# EasyEDA_SCH_BL28Z-3005ZSA04Y_A_Version_B.net
KiCad netlist of a schematic drawn in EasyEDA
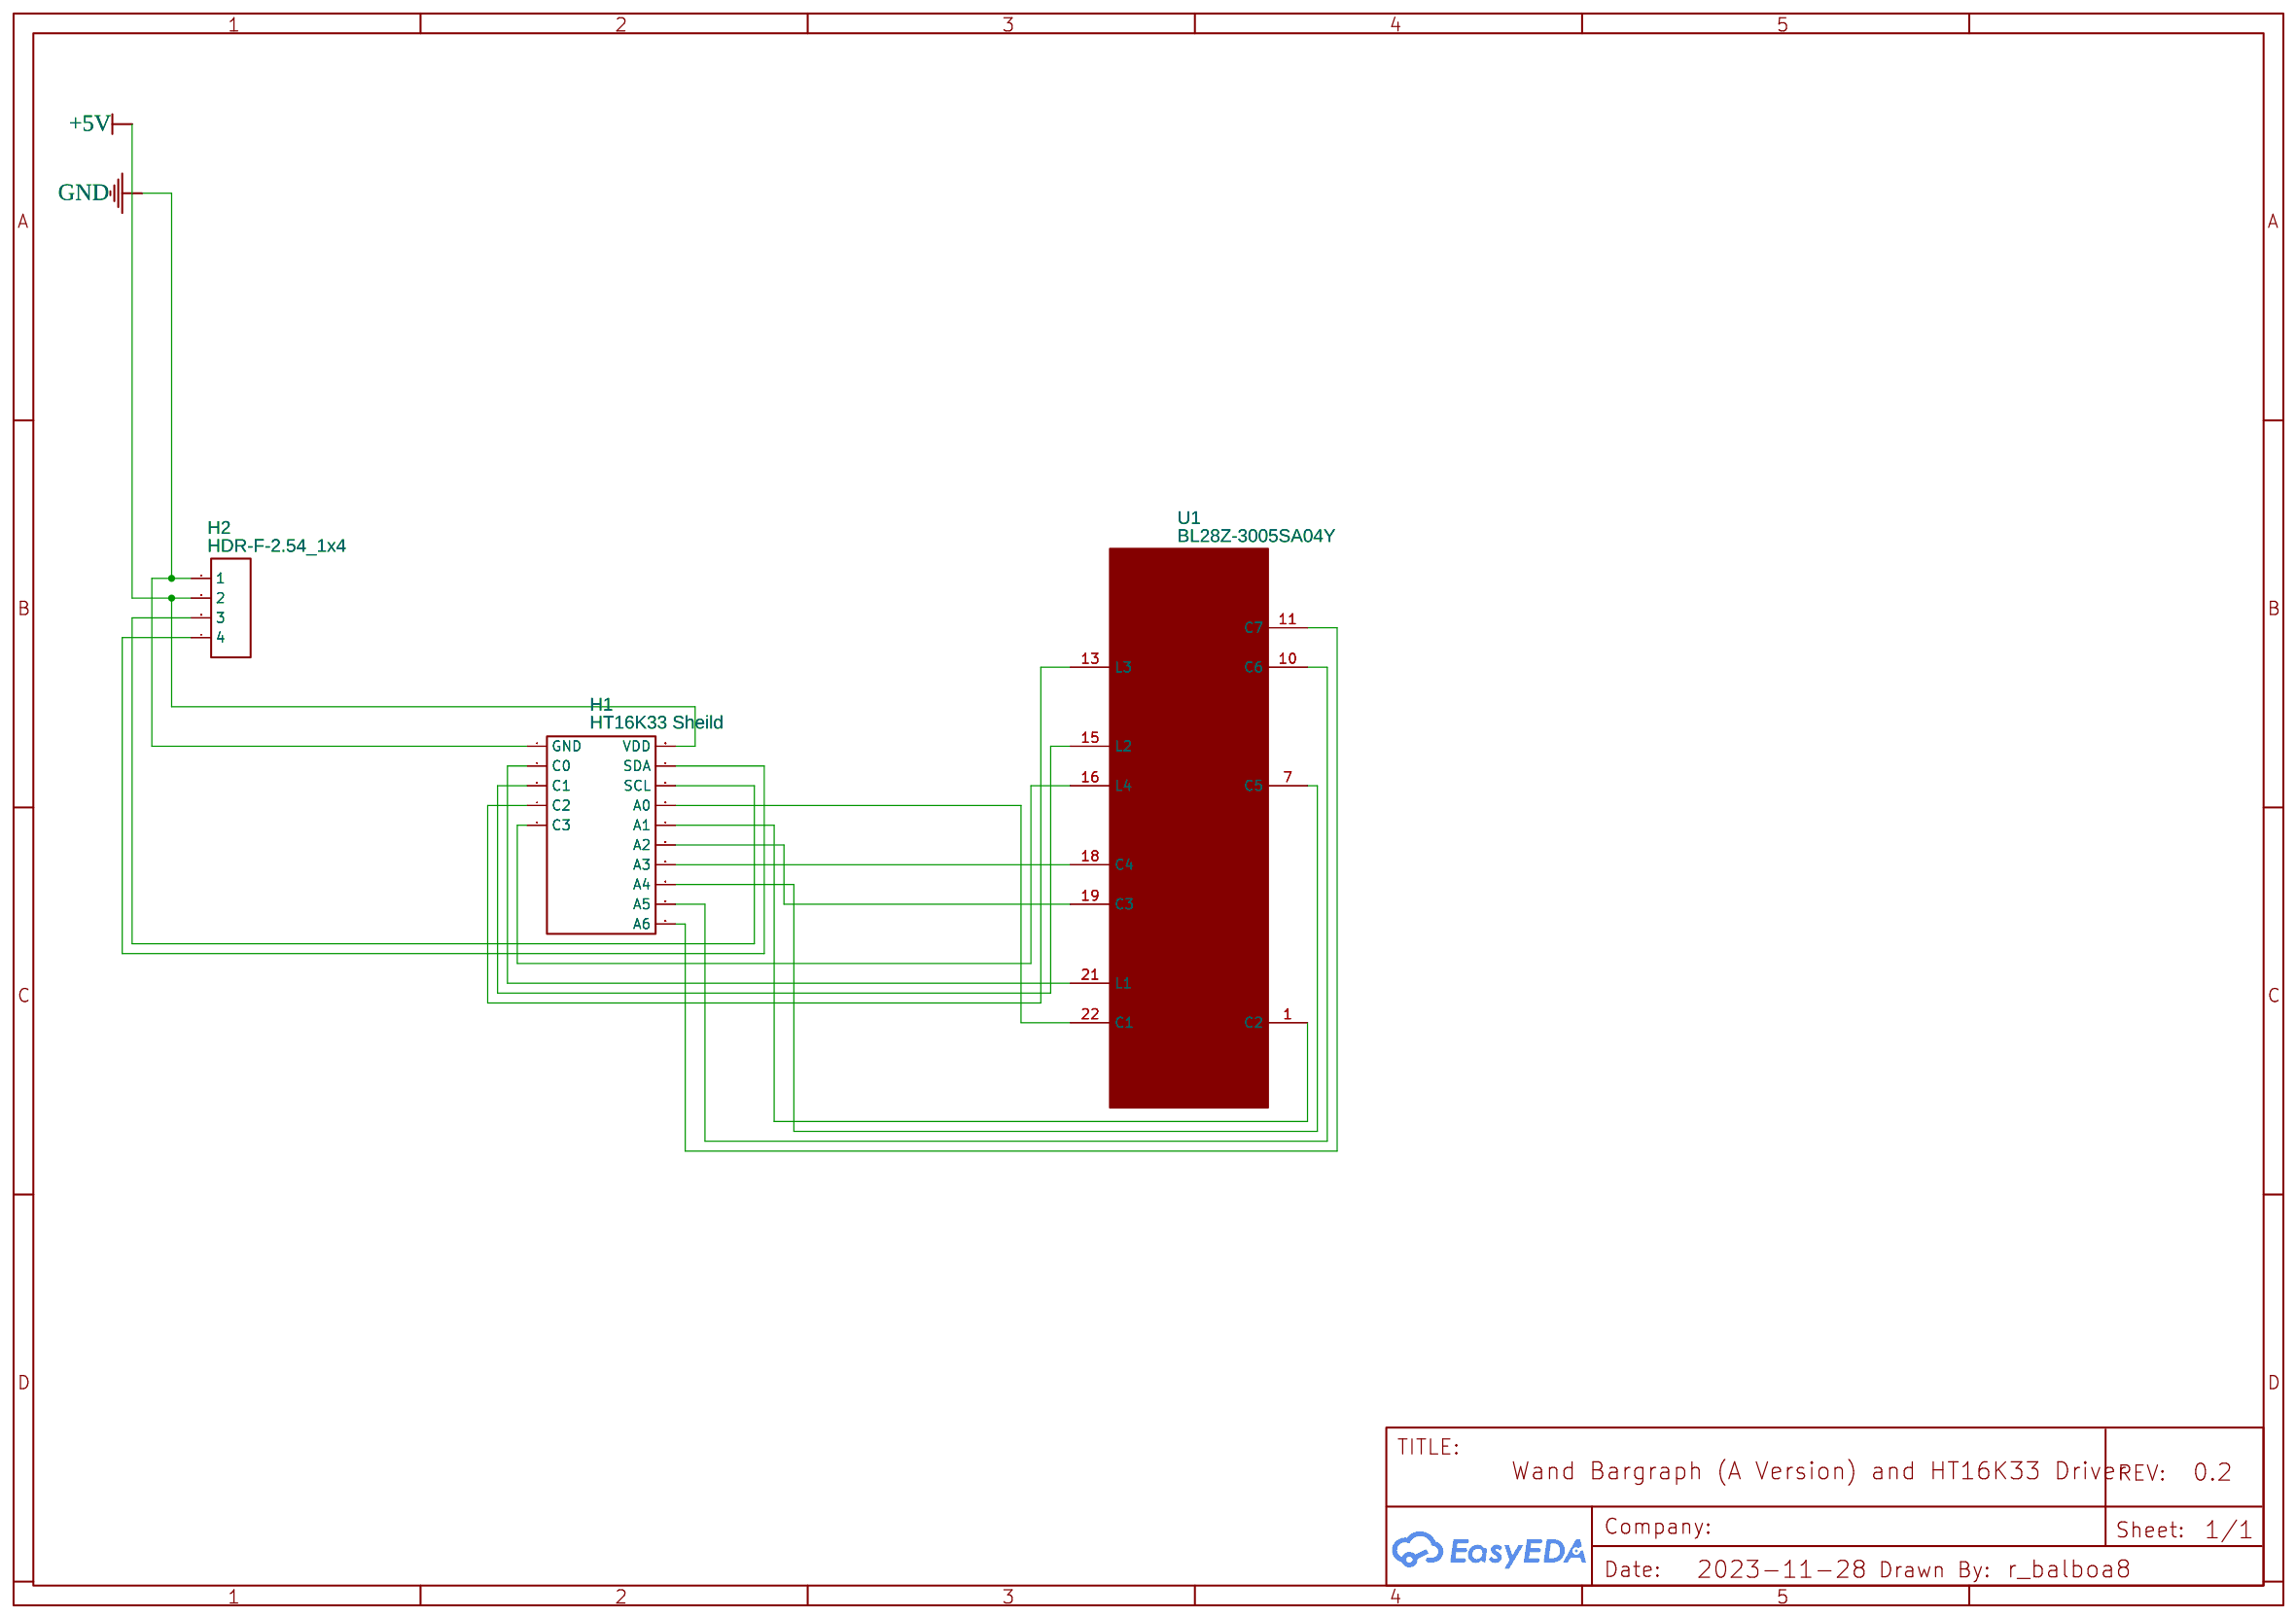
[diagram p0: schematic sheet]

(export (version "E")
  (design (tool "Eeschema 10.0.6"))
  (components
    (comp (ref "H1") (value "HT16K33 Sheild") (libsource (lib "") (part "HT16K33 BL28Z")))
    (comp (ref "H2") (value "HDR-F-2.54_1x4") (libsource (lib "") (part "HDR-F-2.54_1x4")))
    (comp (ref "U1")
      (value "BL28Z-3005SA04Y")
      (fields (field (name "Manufacturer Part") "BL28-3005SDK04") (field (name "Manufacturer") "BARMETER"))
      (libsource (lib "") (part "BL28Z-3005SA04Y"))
    )
  )
  (nets
    (net (code "1") (name "+5V") (class "Default")
      (node (ref "H1") (pin "28") (pinfunction "VDD_28") (pintype "unspecified"))
      (node (ref "H2") (pin "2") (pinfunction "2_2") (pintype "unspecified"))
    )
    (net (code "2") (name "GND") (class "Default")
      (node (ref "H1") (pin "1") (pinfunction "GND_1") (pintype "unspecified"))
      (node (ref "H2") (pin "1") (pinfunction "1_1") (pintype "unspecified"))
    )
    (net (code "3") (name "Net-(H1-A0)") (class "Default")
      (node (ref "H1") (pin "25") (pinfunction "A0_25") (pintype "unspecified"))
      (node (ref "U1") (pin "22") (pinfunction "C1_22") (pintype "unspecified"))
    )
    (net (code "4") (name "Net-(H1-A1)") (class "Default")
      (node (ref "H1") (pin "24") (pinfunction "A1_24") (pintype "unspecified"))
      (node (ref "U1") (pin "1") (pinfunction "C2_1") (pintype "unspecified"))
    )
    (net (code "5") (name "Net-(H1-A2)") (class "Default")
      (node (ref "H1") (pin "23") (pinfunction "A2_23") (pintype "unspecified"))
      (node (ref "U1") (pin "19") (pinfunction "C3_19") (pintype "unspecified"))
    )
    (net (code "6") (name "Net-(H1-A3)") (class "Default")
      (node (ref "H1") (pin "22") (pinfunction "A3_22") (pintype "unspecified"))
      (node (ref "U1") (pin "18") (pinfunction "C4_18") (pintype "unspecified"))
    )
    (net (code "7") (name "Net-(H1-A4)") (class "Default")
      (node (ref "H1") (pin "21") (pinfunction "A4_21") (pintype "unspecified"))
      (node (ref "U1") (pin "7") (pinfunction "C5_7") (pintype "unspecified"))
    )
    (net (code "8") (name "Net-(H1-A5)") (class "Default")
      (node (ref "H1") (pin "20") (pinfunction "A5_20") (pintype "unspecified"))
      (node (ref "U1") (pin "10") (pinfunction "C6_10") (pintype "unspecified"))
    )
    (net (code "9") (name "Net-(H1-A6)") (class "Default")
      (node (ref "H1") (pin "19") (pinfunction "A6_19") (pintype "unspecified"))
      (node (ref "U1") (pin "11") (pinfunction "C7_11") (pintype "unspecified"))
    )
    (net (code "10") (name "Net-(H1-C0)") (class "Default")
      (node (ref "H1") (pin "2") (pinfunction "C0_2") (pintype "unspecified"))
      (node (ref "U1") (pin "21") (pinfunction "L1_21") (pintype "unspecified"))
    )
    (net (code "11") (name "Net-(H1-C1)") (class "Default")
      (node (ref "H1") (pin "3") (pinfunction "C1_3") (pintype "unspecified"))
      (node (ref "U1") (pin "15") (pinfunction "L2_15") (pintype "unspecified"))
    )
    (net (code "12") (name "Net-(H1-C2)") (class "Default")
      (node (ref "H1") (pin "4") (pinfunction "C2_4") (pintype "unspecified"))
      (node (ref "U1") (pin "13") (pinfunction "L3_13") (pintype "unspecified"))
    )
    (net (code "13") (name "Net-(H1-C3)") (class "Default")
      (node (ref "H1") (pin "5") (pinfunction "C3_5") (pintype "unspecified"))
      (node (ref "U1") (pin "16") (pinfunction "L4_16") (pintype "unspecified"))
    )
    (net (code "14") (name "Net-(H1-SCL)") (class "Default")
      (node (ref "H1") (pin "26") (pinfunction "SCL_26") (pintype "unspecified"))
      (node (ref "H2") (pin "3") (pinfunction "3_3") (pintype "unspecified"))
    )
    (net (code "15") (name "Net-(H1-SDA)") (class "Default")
      (node (ref "H1") (pin "27") (pinfunction "SDA_27") (pintype "unspecified"))
      (node (ref "H2") (pin "4") (pinfunction "4_4") (pintype "unspecified"))
    )
  )
)
